# TCC_COMPLETO-jalim31.net
KiCad netlist of a schematic drawn in EAGLE
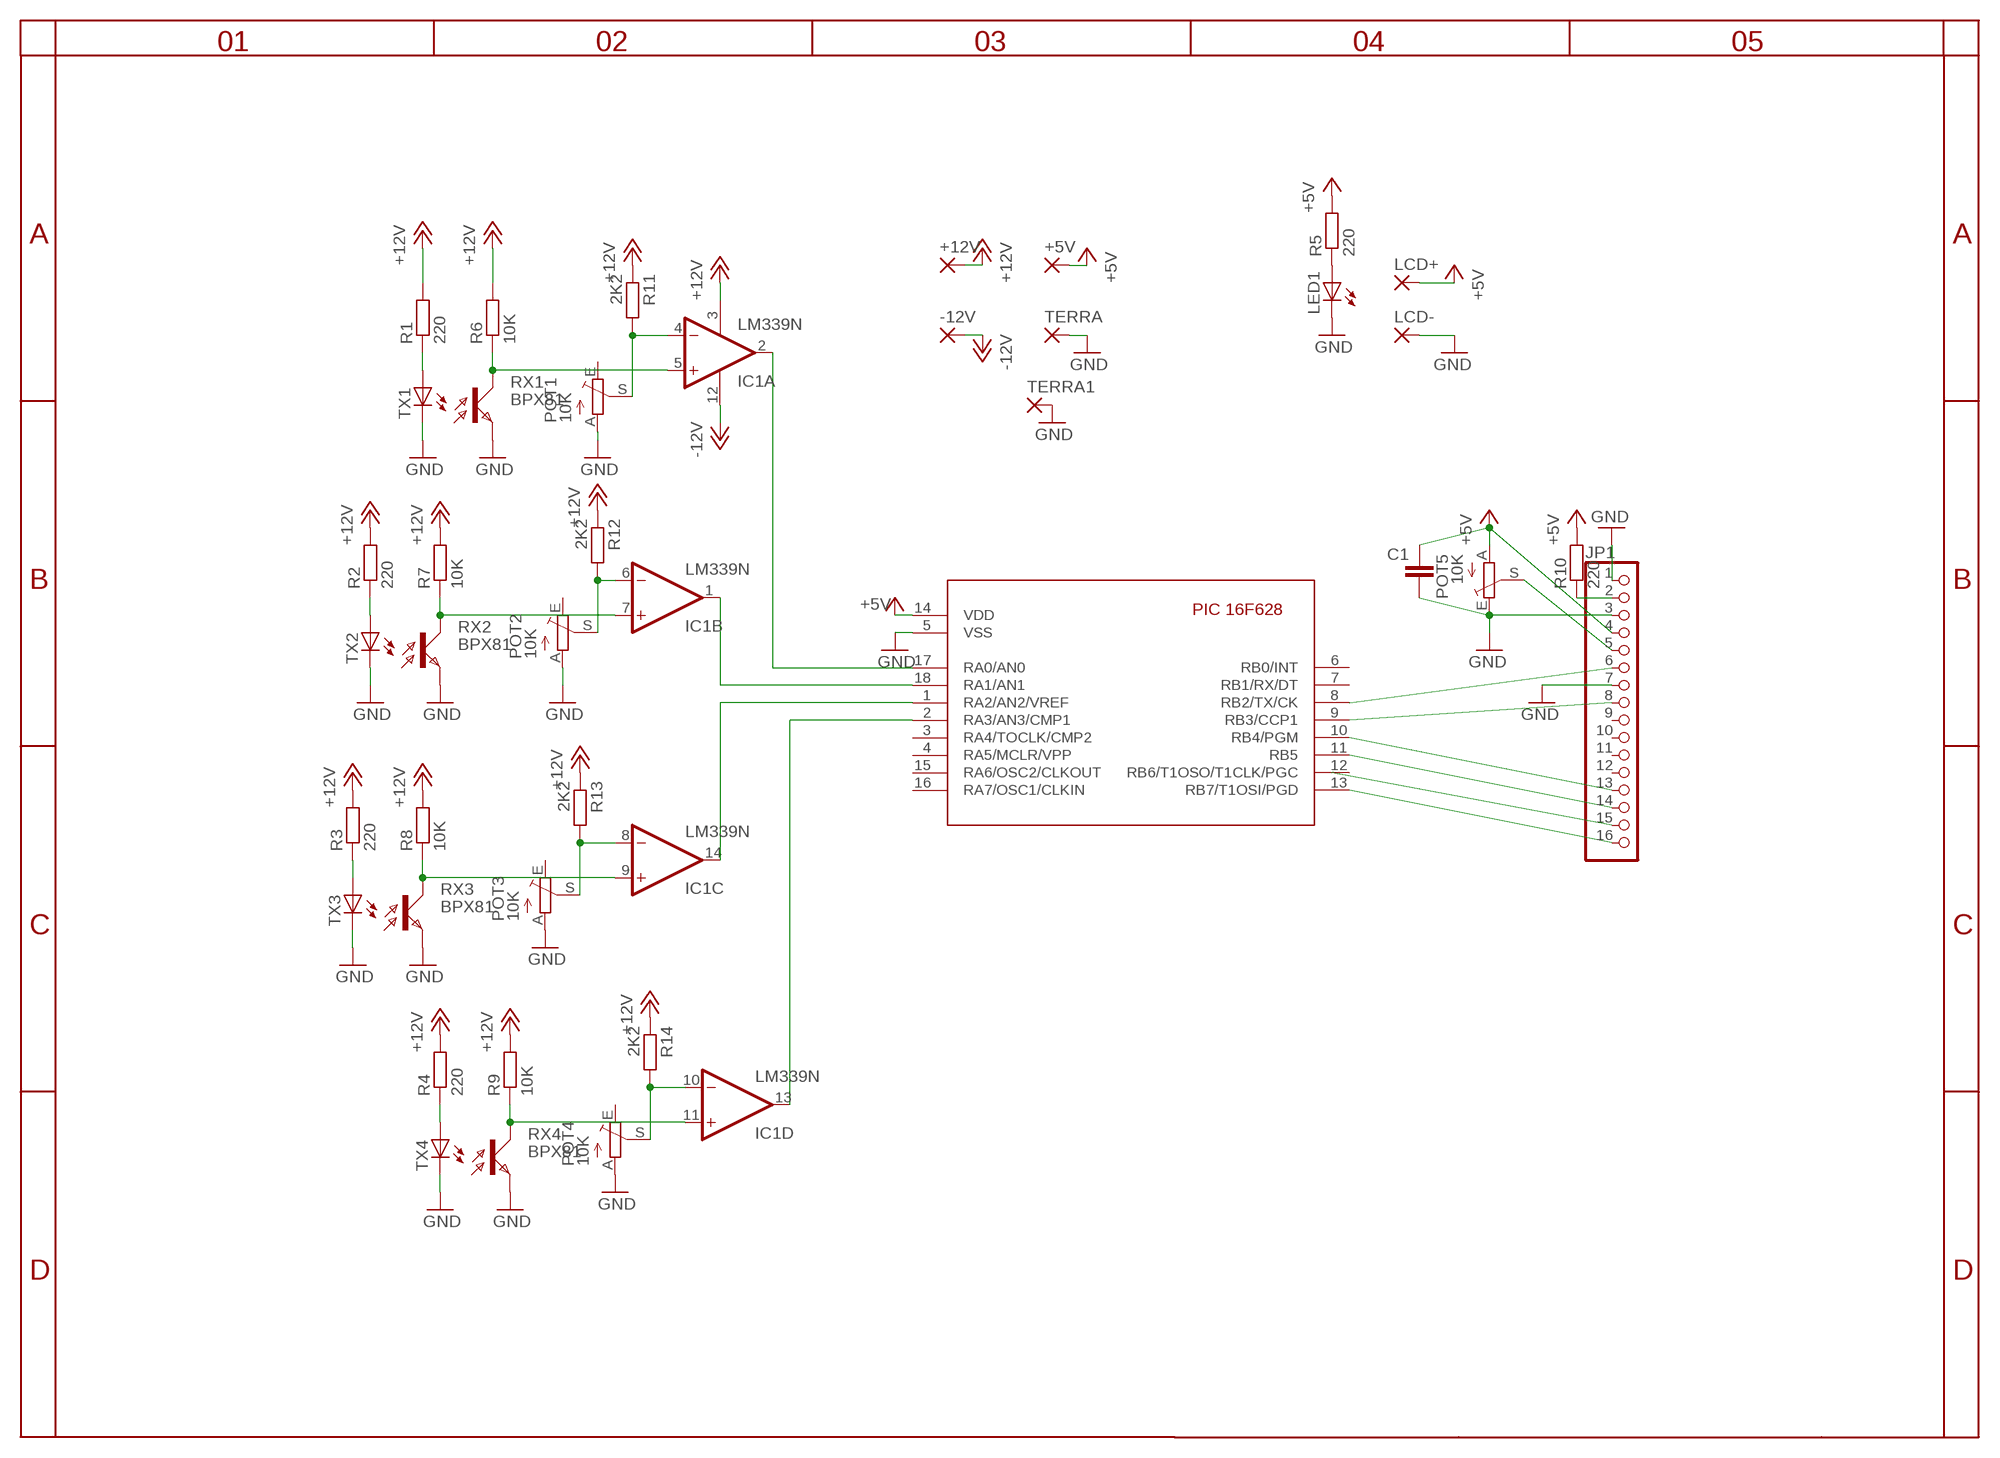
[diagram p0: schematic, sheet 1]

(export (version "E")
  (design (tool "Eeschema 10.0.6"))
  (components
    (comp (ref "+5V")
      (value "2,54/1,0")
      (footprint "eagle-import:2,54_1,0")
      (libsource (lib "eagle-import") (part "2,54/1,0"))
    )
    (comp (ref "+12V")
      (value "2,54/1,0")
      (footprint "eagle-import:2,54_1,0")
      (libsource (lib "eagle-import") (part "2,54/1,0"))
    )
    (comp (ref "-12V")
      (value "2,54/1,0")
      (footprint "eagle-import:2,54_1,0")
      (libsource (lib "eagle-import") (part "2,54/1,0"))
    )
    (comp (ref "C1")
      (value "C-EU025-030X050")
      (footprint "eagle-import:C025-030X050")
      (libsource (lib "eagle-import") (part "C-EU025-030X050"))
    )
    (comp (ref "IC1")
      (value "LM339N")
      (footprint "eagle-import:DIL14")
      (libsource (lib "eagle-import") (part "LM339N"))
    )
    (comp (ref "JP1")
      (value "PINHD-1X16")
      (footprint "eagle-import:1X16")
      (libsource (lib "eagle-import") (part "PINHD-1X16"))
    )
    (comp (ref "LCD+")
      (value "2,54/1,0")
      (footprint "eagle-import:2,54_1,0")
      (libsource (lib "eagle-import") (part "2,54/1,0"))
    )
    (comp (ref "LCD-")
      (value "2,54/1,0")
      (footprint "eagle-import:2,54_1,0")
      (libsource (lib "eagle-import") (part "2,54/1,0"))
    )
    (comp (ref "LED1")
      (value "LED5MM")
      (footprint "eagle-import:LED5MM")
      (libsource (lib "eagle-import") (part "LED5MM"))
    )
    (comp (ref "POT1")
      (value "10K")
      (footprint "eagle-import:LI10")
      (libsource (lib "eagle-import") (part "TRIM_EU-LI10"))
    )
    (comp (ref "POT2")
      (value "10K")
      (footprint "eagle-import:LI10")
      (libsource (lib "eagle-import") (part "TRIM_EU-LI10"))
    )
    (comp (ref "POT3")
      (value "10K")
      (footprint "eagle-import:LI10")
      (libsource (lib "eagle-import") (part "TRIM_EU-LI10"))
    )
    (comp (ref "POT4")
      (value "10K")
      (footprint "eagle-import:LI10")
      (libsource (lib "eagle-import") (part "TRIM_EU-LI10"))
    )
    (comp (ref "POT5")
      (value "10K")
      (footprint "eagle-import:LI10")
      (libsource (lib "eagle-import") (part "TRIM_EU-LI10"))
    )
    (comp (ref "R1")
      (value "220")
      (footprint "eagle-import:0207_10")
      (libsource (lib "eagle-import") (part "R-EU_0207/10"))
    )
    (comp (ref "R2")
      (value "220")
      (footprint "eagle-import:0207_10")
      (libsource (lib "eagle-import") (part "R-EU_0207/10"))
    )
    (comp (ref "R3")
      (value "220")
      (footprint "eagle-import:0207_10")
      (libsource (lib "eagle-import") (part "R-EU_0207/10"))
    )
    (comp (ref "R4")
      (value "220")
      (footprint "eagle-import:0207_10")
      (libsource (lib "eagle-import") (part "R-EU_0207/10"))
    )
    (comp (ref "R5")
      (value "220")
      (footprint "eagle-import:0207_10")
      (libsource (lib "eagle-import") (part "R-EU_0207/10"))
    )
    (comp (ref "R6")
      (value "10K")
      (footprint "eagle-import:0207_10")
      (libsource (lib "eagle-import") (part "R-EU_0207/10"))
    )
    (comp (ref "R7")
      (value "10K")
      (footprint "eagle-import:0207_10")
      (libsource (lib "eagle-import") (part "R-EU_0207/10"))
    )
    (comp (ref "R8")
      (value "10K")
      (footprint "eagle-import:0207_10")
      (libsource (lib "eagle-import") (part "R-EU_0207/10"))
    )
    (comp (ref "R9")
      (value "10K")
      (footprint "eagle-import:0207_10")
      (libsource (lib "eagle-import") (part "R-EU_0207/10"))
    )
    (comp (ref "R10")
      (value "220")
      (footprint "eagle-import:0207_10")
      (libsource (lib "eagle-import") (part "R-EU_0207/10"))
    )
    (comp (ref "R11")
      (value "2K2")
      (footprint "eagle-import:0207_10")
      (libsource (lib "eagle-import") (part "R-EU_0207/10"))
    )
    (comp (ref "R12")
      (value "2K2")
      (footprint "eagle-import:0207_10")
      (libsource (lib "eagle-import") (part "R-EU_0207/10"))
    )
    (comp (ref "R13")
      (value "2K2")
      (footprint "eagle-import:0207_10")
      (libsource (lib "eagle-import") (part "R-EU_0207/10"))
    )
    (comp (ref "R14")
      (value "2K2")
      (footprint "eagle-import:0207_10")
      (libsource (lib "eagle-import") (part "R-EU_0207/10"))
    )
    (comp (ref "RX1")
      (value "BPX81")
      (footprint "eagle-import:BPX81")
      (libsource (lib "eagle-import") (part "BPX81"))
    )
    (comp (ref "RX2")
      (value "BPX81")
      (footprint "eagle-import:BPX81")
      (libsource (lib "eagle-import") (part "BPX81"))
    )
    (comp (ref "RX3")
      (value "BPX81")
      (footprint "eagle-import:BPX81")
      (libsource (lib "eagle-import") (part "BPX81"))
    )
    (comp (ref "RX4")
      (value "BPX81")
      (footprint "eagle-import:BPX81")
      (libsource (lib "eagle-import") (part "BPX81"))
    )
    (comp (ref "TERRA")
      (value "2,54/1,0")
      (footprint "eagle-import:2,54_1,0")
      (libsource (lib "eagle-import") (part "2,54/1,0"))
    )
    (comp (ref "TERRA1")
      (value "2,54/1,0")
      (footprint "eagle-import:2,54_1,0")
      (libsource (lib "eagle-import") (part "2,54/1,0"))
    )
    (comp (ref "TX1")
      (value "LED5MM")
      (footprint "eagle-import:LED5MM")
      (libsource (lib "eagle-import") (part "LED5MM"))
    )
    (comp (ref "TX2")
      (value "LED5MM")
      (footprint "eagle-import:LED5MM")
      (libsource (lib "eagle-import") (part "LED5MM"))
    )
    (comp (ref "TX3")
      (value "LED5MM")
      (footprint "eagle-import:LED5MM")
      (libsource (lib "eagle-import") (part "LED5MM"))
    )
    (comp (ref "TX4")
      (value "LED5MM")
      (footprint "eagle-import:LED5MM")
      (libsource (lib "eagle-import") (part "LED5MM"))
    )
    (comp (ref "U$1")
      (value "16F628")
      (footprint "eagle-import:PIC16F628-18-LEAD-PDIP")
      (libsource (lib "eagle-import") (part "16F628"))
    )
  )
  (nets
    (net (code "1") (name "+5V") (class "Default")
      (node (ref "+5V") (pin "1") (pinfunction "P_1") (pintype "passive"))
      (node (ref "C1") (pin "1") (pinfunction "1_1") (pintype "passive"))
      (node (ref "JP1") (pin "4") (pinfunction "4_4") (pintype "passive"))
      (node (ref "LCD+") (pin "1") (pinfunction "P_1") (pintype "passive"))
      (node (ref "POT5") (pin "A") (pinfunction "A_A") (pintype "passive"))
      (node (ref "R10") (pin "2") (pinfunction "2_2") (pintype "passive"))
      (node (ref "R5") (pin "2") (pinfunction "2_2") (pintype "passive"))
      (node (ref "U$1") (pin "14") (pinfunction "VDD_14") (pintype "input"))
    )
    (net (code "2") (name "+12V") (class "Default")
      (node (ref "+12V") (pin "1") (pinfunction "P_1") (pintype "passive"))
      (node (ref "IC1") (pin "3") (pinfunction "V+_3") (pintype "power_in"))
      (node (ref "R1") (pin "2") (pinfunction "2_2") (pintype "passive"))
      (node (ref "R11") (pin "1") (pinfunction "1_1") (pintype "passive"))
      (node (ref "R12") (pin "1") (pinfunction "1_1") (pintype "passive"))
      (node (ref "R13") (pin "1") (pinfunction "1_1") (pintype "passive"))
      (node (ref "R14") (pin "1") (pinfunction "1_1") (pintype "passive"))
      (node (ref "R2") (pin "2") (pinfunction "2_2") (pintype "passive"))
      (node (ref "R3") (pin "2") (pinfunction "2_2") (pintype "passive"))
      (node (ref "R4") (pin "2") (pinfunction "2_2") (pintype "passive"))
      (node (ref "R6") (pin "2") (pinfunction "2_2") (pintype "passive"))
      (node (ref "R7") (pin "2") (pinfunction "2_2") (pintype "passive"))
      (node (ref "R8") (pin "2") (pinfunction "2_2") (pintype "passive"))
      (node (ref "R9") (pin "2") (pinfunction "2_2") (pintype "passive"))
    )
    (net (code "3") (name "-12V") (class "Default")
      (node (ref "-12V") (pin "1") (pinfunction "P_1") (pintype "passive"))
      (node (ref "IC1") (pin "12") (pinfunction "GND_12") (pintype "power_in"))
    )
    (net (code "4") (name "GND") (class "Default")
      (node (ref "C1") (pin "2") (pinfunction "2_2") (pintype "passive"))
      (node (ref "JP1") (pin "1") (pinfunction "1_1") (pintype "passive"))
      (node (ref "JP1") (pin "3") (pinfunction "3_3") (pintype "passive"))
      (node (ref "JP1") (pin "7") (pinfunction "7_7") (pintype "passive"))
      (node (ref "LCD-") (pin "1") (pinfunction "P_1") (pintype "passive"))
      (node (ref "LED1") (pin "K") (pinfunction "C_K") (pintype "passive"))
      (node (ref "POT1") (pin "A") (pinfunction "A_A") (pintype "passive"))
      (node (ref "POT2") (pin "A") (pinfunction "A_A") (pintype "passive"))
      (node (ref "POT3") (pin "A") (pinfunction "A_A") (pintype "passive"))
      (node (ref "POT4") (pin "A") (pinfunction "A_A") (pintype "passive"))
      (node (ref "POT5") (pin "E") (pinfunction "E_E") (pintype "passive"))
      (node (ref "RX1") (pin "E") (pinfunction "E_E") (pintype "passive"))
      (node (ref "RX2") (pin "E") (pinfunction "E_E") (pintype "passive"))
      (node (ref "RX3") (pin "E") (pinfunction "E_E") (pintype "passive"))
      (node (ref "RX4") (pin "E") (pinfunction "E_E") (pintype "passive"))
      (node (ref "TERRA") (pin "1") (pinfunction "P_1") (pintype "passive"))
      (node (ref "TERRA1") (pin "1") (pinfunction "P_1") (pintype "passive"))
      (node (ref "TX1") (pin "K") (pinfunction "C_K") (pintype "passive"))
      (node (ref "TX2") (pin "K") (pinfunction "C_K") (pintype "passive"))
      (node (ref "TX3") (pin "K") (pinfunction "C_K") (pintype "passive"))
      (node (ref "TX4") (pin "K") (pinfunction "C_K") (pintype "passive"))
      (node (ref "U$1") (pin "5") (pinfunction "VSS_5") (pintype "input"))
    )
    (net (code "5") (name "Net-(IC1A-+IN)") (class "Default")
      (node (ref "IC1") (pin "5") (pinfunction "+IN_5") (pintype "input"))
      (node (ref "R6") (pin "1") (pinfunction "1_1") (pintype "passive"))
      (node (ref "RX1") (pin "C") (pinfunction "C_C") (pintype "passive"))
    )
    (net (code "6") (name "Net-(IC1A--IN)") (class "Default")
      (node (ref "IC1") (pin "4") (pinfunction "-IN_4") (pintype "input"))
      (node (ref "POT1") (pin "S") (pinfunction "S_S") (pintype "passive"))
      (node (ref "R11") (pin "2") (pinfunction "2_2") (pintype "passive"))
    )
    (net (code "7") (name "Net-(IC1A-OUT)") (class "Default")
      (node (ref "IC1") (pin "2") (pinfunction "OUT_2") (pintype "open_collector"))
      (node (ref "U$1") (pin "17") (pinfunction "RA0/AN0_17") (pintype "bidirectional"))
    )
    (net (code "8") (name "Net-(IC1B-+IN)") (class "Default")
      (node (ref "IC1") (pin "7") (pinfunction "+IN_7") (pintype "input"))
      (node (ref "R7") (pin "1") (pinfunction "1_1") (pintype "passive"))
      (node (ref "RX2") (pin "C") (pinfunction "C_C") (pintype "passive"))
    )
    (net (code "9") (name "Net-(IC1B--IN)") (class "Default")
      (node (ref "IC1") (pin "6") (pinfunction "-IN_6") (pintype "input"))
      (node (ref "POT2") (pin "S") (pinfunction "S_S") (pintype "passive"))
      (node (ref "R12") (pin "2") (pinfunction "2_2") (pintype "passive"))
    )
    (net (code "10") (name "Net-(IC1B-OUT)") (class "Default")
      (node (ref "IC1") (pin "1") (pinfunction "OUT_1") (pintype "open_collector"))
      (node (ref "U$1") (pin "18") (pinfunction "RA1/AN1_18") (pintype "bidirectional"))
    )
    (net (code "11") (name "Net-(IC1C-+IN)") (class "Default")
      (node (ref "IC1") (pin "9") (pinfunction "+IN_9") (pintype "input"))
      (node (ref "R8") (pin "1") (pinfunction "1_1") (pintype "passive"))
      (node (ref "RX3") (pin "C") (pinfunction "C_C") (pintype "passive"))
    )
    (net (code "12") (name "Net-(IC1C--IN)") (class "Default")
      (node (ref "IC1") (pin "8") (pinfunction "-IN_8") (pintype "input"))
      (node (ref "POT3") (pin "S") (pinfunction "S_S") (pintype "passive"))
      (node (ref "R13") (pin "2") (pinfunction "2_2") (pintype "passive"))
    )
    (net (code "13") (name "Net-(IC1C-OUT)") (class "Default")
      (node (ref "IC1") (pin "14") (pinfunction "OUT_14") (pintype "open_collector"))
      (node (ref "U$1") (pin "1") (pinfunction "RA2/AN2/VREF_1") (pintype "bidirectional"))
    )
    (net (code "14") (name "Net-(IC1D-+IN)") (class "Default")
      (node (ref "IC1") (pin "11") (pinfunction "+IN_11") (pintype "input"))
      (node (ref "R9") (pin "1") (pinfunction "1_1") (pintype "passive"))
      (node (ref "RX4") (pin "C") (pinfunction "C_C") (pintype "passive"))
    )
    (net (code "15") (name "Net-(IC1D--IN)") (class "Default")
      (node (ref "IC1") (pin "10") (pinfunction "-IN_10") (pintype "input"))
      (node (ref "POT4") (pin "S") (pinfunction "S_S") (pintype "passive"))
      (node (ref "R14") (pin "2") (pinfunction "2_2") (pintype "passive"))
    )
    (net (code "16") (name "Net-(IC1D-OUT)") (class "Default")
      (node (ref "IC1") (pin "13") (pinfunction "OUT_13") (pintype "open_collector"))
      (node (ref "U$1") (pin "2") (pinfunction "RA3/AN3/CMP1_2") (pintype "bidirectional"))
    )
    (net (code "17") (name "Net-(JP1-Pad2)") (class "Default")
      (node (ref "JP1") (pin "2") (pinfunction "2_2") (pintype "passive"))
      (node (ref "R10") (pin "1") (pinfunction "1_1") (pintype "passive"))
    )
    (net (code "18") (name "Net-(JP1-Pad5)") (class "Default")
      (node (ref "JP1") (pin "5") (pinfunction "5_5") (pintype "passive"))
      (node (ref "POT5") (pin "S") (pinfunction "S_S") (pintype "passive"))
    )
    (net (code "19") (name "Net-(LED1-PadA)") (class "Default")
      (node (ref "LED1") (pin "A") (pinfunction "A_A") (pintype "passive"))
      (node (ref "R5") (pin "1") (pinfunction "1_1") (pintype "passive"))
    )
    (net (code "20") (name "Net-(R1-Pad1)") (class "Default")
      (node (ref "R1") (pin "1") (pinfunction "1_1") (pintype "passive"))
      (node (ref "TX1") (pin "A") (pinfunction "A_A") (pintype "passive"))
    )
    (net (code "21") (name "Net-(R2-Pad1)") (class "Default")
      (node (ref "R2") (pin "1") (pinfunction "1_1") (pintype "passive"))
      (node (ref "TX2") (pin "A") (pinfunction "A_A") (pintype "passive"))
    )
    (net (code "22") (name "Net-(R3-Pad1)") (class "Default")
      (node (ref "R3") (pin "1") (pinfunction "1_1") (pintype "passive"))
      (node (ref "TX3") (pin "A") (pinfunction "A_A") (pintype "passive"))
    )
    (net (code "23") (name "Net-(R4-Pad1)") (class "Default")
      (node (ref "R4") (pin "1") (pinfunction "1_1") (pintype "passive"))
      (node (ref "TX4") (pin "A") (pinfunction "A_A") (pintype "passive"))
    )
    (net (code "24") (name "Net-(U$1-RB2{slash}TX{slash}CK)") (class "Default")
      (node (ref "JP1") (pin "6") (pinfunction "6_6") (pintype "passive"))
      (node (ref "U$1") (pin "8") (pinfunction "RB2/TX/CK_8") (pintype "bidirectional"))
    )
    (net (code "25") (name "Net-(U$1-RB3{slash}CCP1)") (class "Default")
      (node (ref "JP1") (pin "8") (pinfunction "8_8") (pintype "passive"))
      (node (ref "U$1") (pin "9") (pinfunction "RB3/CCP1_9") (pintype "bidirectional"))
    )
    (net (code "26") (name "Net-(U$1-RB4{slash}PGM)") (class "Default")
      (node (ref "JP1") (pin "13") (pinfunction "13_13") (pintype "passive"))
      (node (ref "U$1") (pin "10") (pinfunction "RB4/PGM_10") (pintype "bidirectional"))
    )
    (net (code "27") (name "Net-(U$1-RB5)") (class "Default")
      (node (ref "JP1") (pin "14") (pinfunction "14_14") (pintype "passive"))
      (node (ref "U$1") (pin "11") (pinfunction "RB5_11") (pintype "bidirectional"))
    )
    (net (code "28") (name "Net-(U$1-RB7{slash}T1OSI{slash}PGD)") (class "Default")
      (node (ref "JP1") (pin "16") (pinfunction "16_16") (pintype "passive"))
      (node (ref "U$1") (pin "13") (pinfunction "RB7/T1OSI/PGD_13") (pintype "bidirectional"))
    )
    (net (code "29") (name "unconnected-(JP1-Pad9)") (class "Default")
      (node (ref "JP1") (pin "9") (pinfunction "9_9") (pintype "passive"))
    )
    (net (code "30") (name "unconnected-(JP1-Pad10)") (class "Default")
      (node (ref "JP1") (pin "10") (pinfunction "10_10") (pintype "passive"))
    )
    (net (code "31") (name "unconnected-(JP1-Pad11)") (class "Default")
      (node (ref "JP1") (pin "11") (pinfunction "11_11") (pintype "passive"))
    )
    (net (code "32") (name "unconnected-(JP1-Pad12)") (class "Default")
      (node (ref "JP1") (pin "12") (pinfunction "12_12") (pintype "passive"))
    )
    (net (code "33") (name "unconnected-(JP1-Pad15)") (class "Default")
      (node (ref "JP1") (pin "15") (pinfunction "15_15") (pintype "passive"))
    )
    (net (code "34") (name "unconnected-(POT1-PadE)") (class "Default")
      (node (ref "POT1") (pin "E") (pinfunction "E_E") (pintype "passive"))
    )
    (net (code "35") (name "unconnected-(POT2-PadE)") (class "Default")
      (node (ref "POT2") (pin "E") (pinfunction "E_E") (pintype "passive"))
    )
    (net (code "36") (name "unconnected-(POT3-PadE)") (class "Default")
      (node (ref "POT3") (pin "E") (pinfunction "E_E") (pintype "passive"))
    )
    (net (code "37") (name "unconnected-(POT4-PadE)") (class "Default")
      (node (ref "POT4") (pin "E") (pinfunction "E_E") (pintype "passive"))
    )
    (net (code "38") (name "unconnected-(U$1-RA4{slash}TOCLK{slash}CMP2-Pad3)") (class "Default")
      (node (ref "U$1") (pin "3") (pinfunction "RA4/TOCLK/CMP2_3") (pintype "bidirectional"))
    )
    (net (code "39") (name "unconnected-(U$1-RA5{slash}MCLR{slash}VPP-Pad4)") (class "Default")
      (node (ref "U$1") (pin "4") (pinfunction "RA5/MCLR/VPP_4") (pintype "bidirectional"))
    )
    (net (code "40") (name "unconnected-(U$1-RA6{slash}OSC2{slash}CLKOUT-Pad15)") (class "Default")
      (node (ref "U$1") (pin "15") (pinfunction "RA6/OSC2/CLKOUT_15") (pintype "bidirectional"))
    )
    (net (code "41") (name "unconnected-(U$1-RA7{slash}OSC1{slash}CLKIN-Pad16)") (class "Default")
      (node (ref "U$1") (pin "16") (pinfunction "RA7/OSC1/CLKIN_16") (pintype "bidirectional"))
    )
    (net (code "42") (name "unconnected-(U$1-RB0{slash}INT-Pad6)") (class "Default")
      (node (ref "U$1") (pin "6") (pinfunction "RB0/INT_6") (pintype "bidirectional"))
    )
    (net (code "43") (name "unconnected-(U$1-RB1{slash}RX{slash}DT-Pad7)") (class "Default")
      (node (ref "U$1") (pin "7") (pinfunction "RB1/RX/DT_7") (pintype "bidirectional"))
    )
    (net (code "44") (name "unconnected-(U$1-RB6{slash}T1OSO{slash}T1CLK{slash}PGC-Pad12)") (class "Default")
      (node (ref "U$1") (pin "12") (pinfunction "RB6/T1OSO/T1CLK/PGC_12") (pintype "bidirectional"))
    )
  )
)
